# 3yp_project.net
KiCad netlist of a schematic drawn in EasyEDA
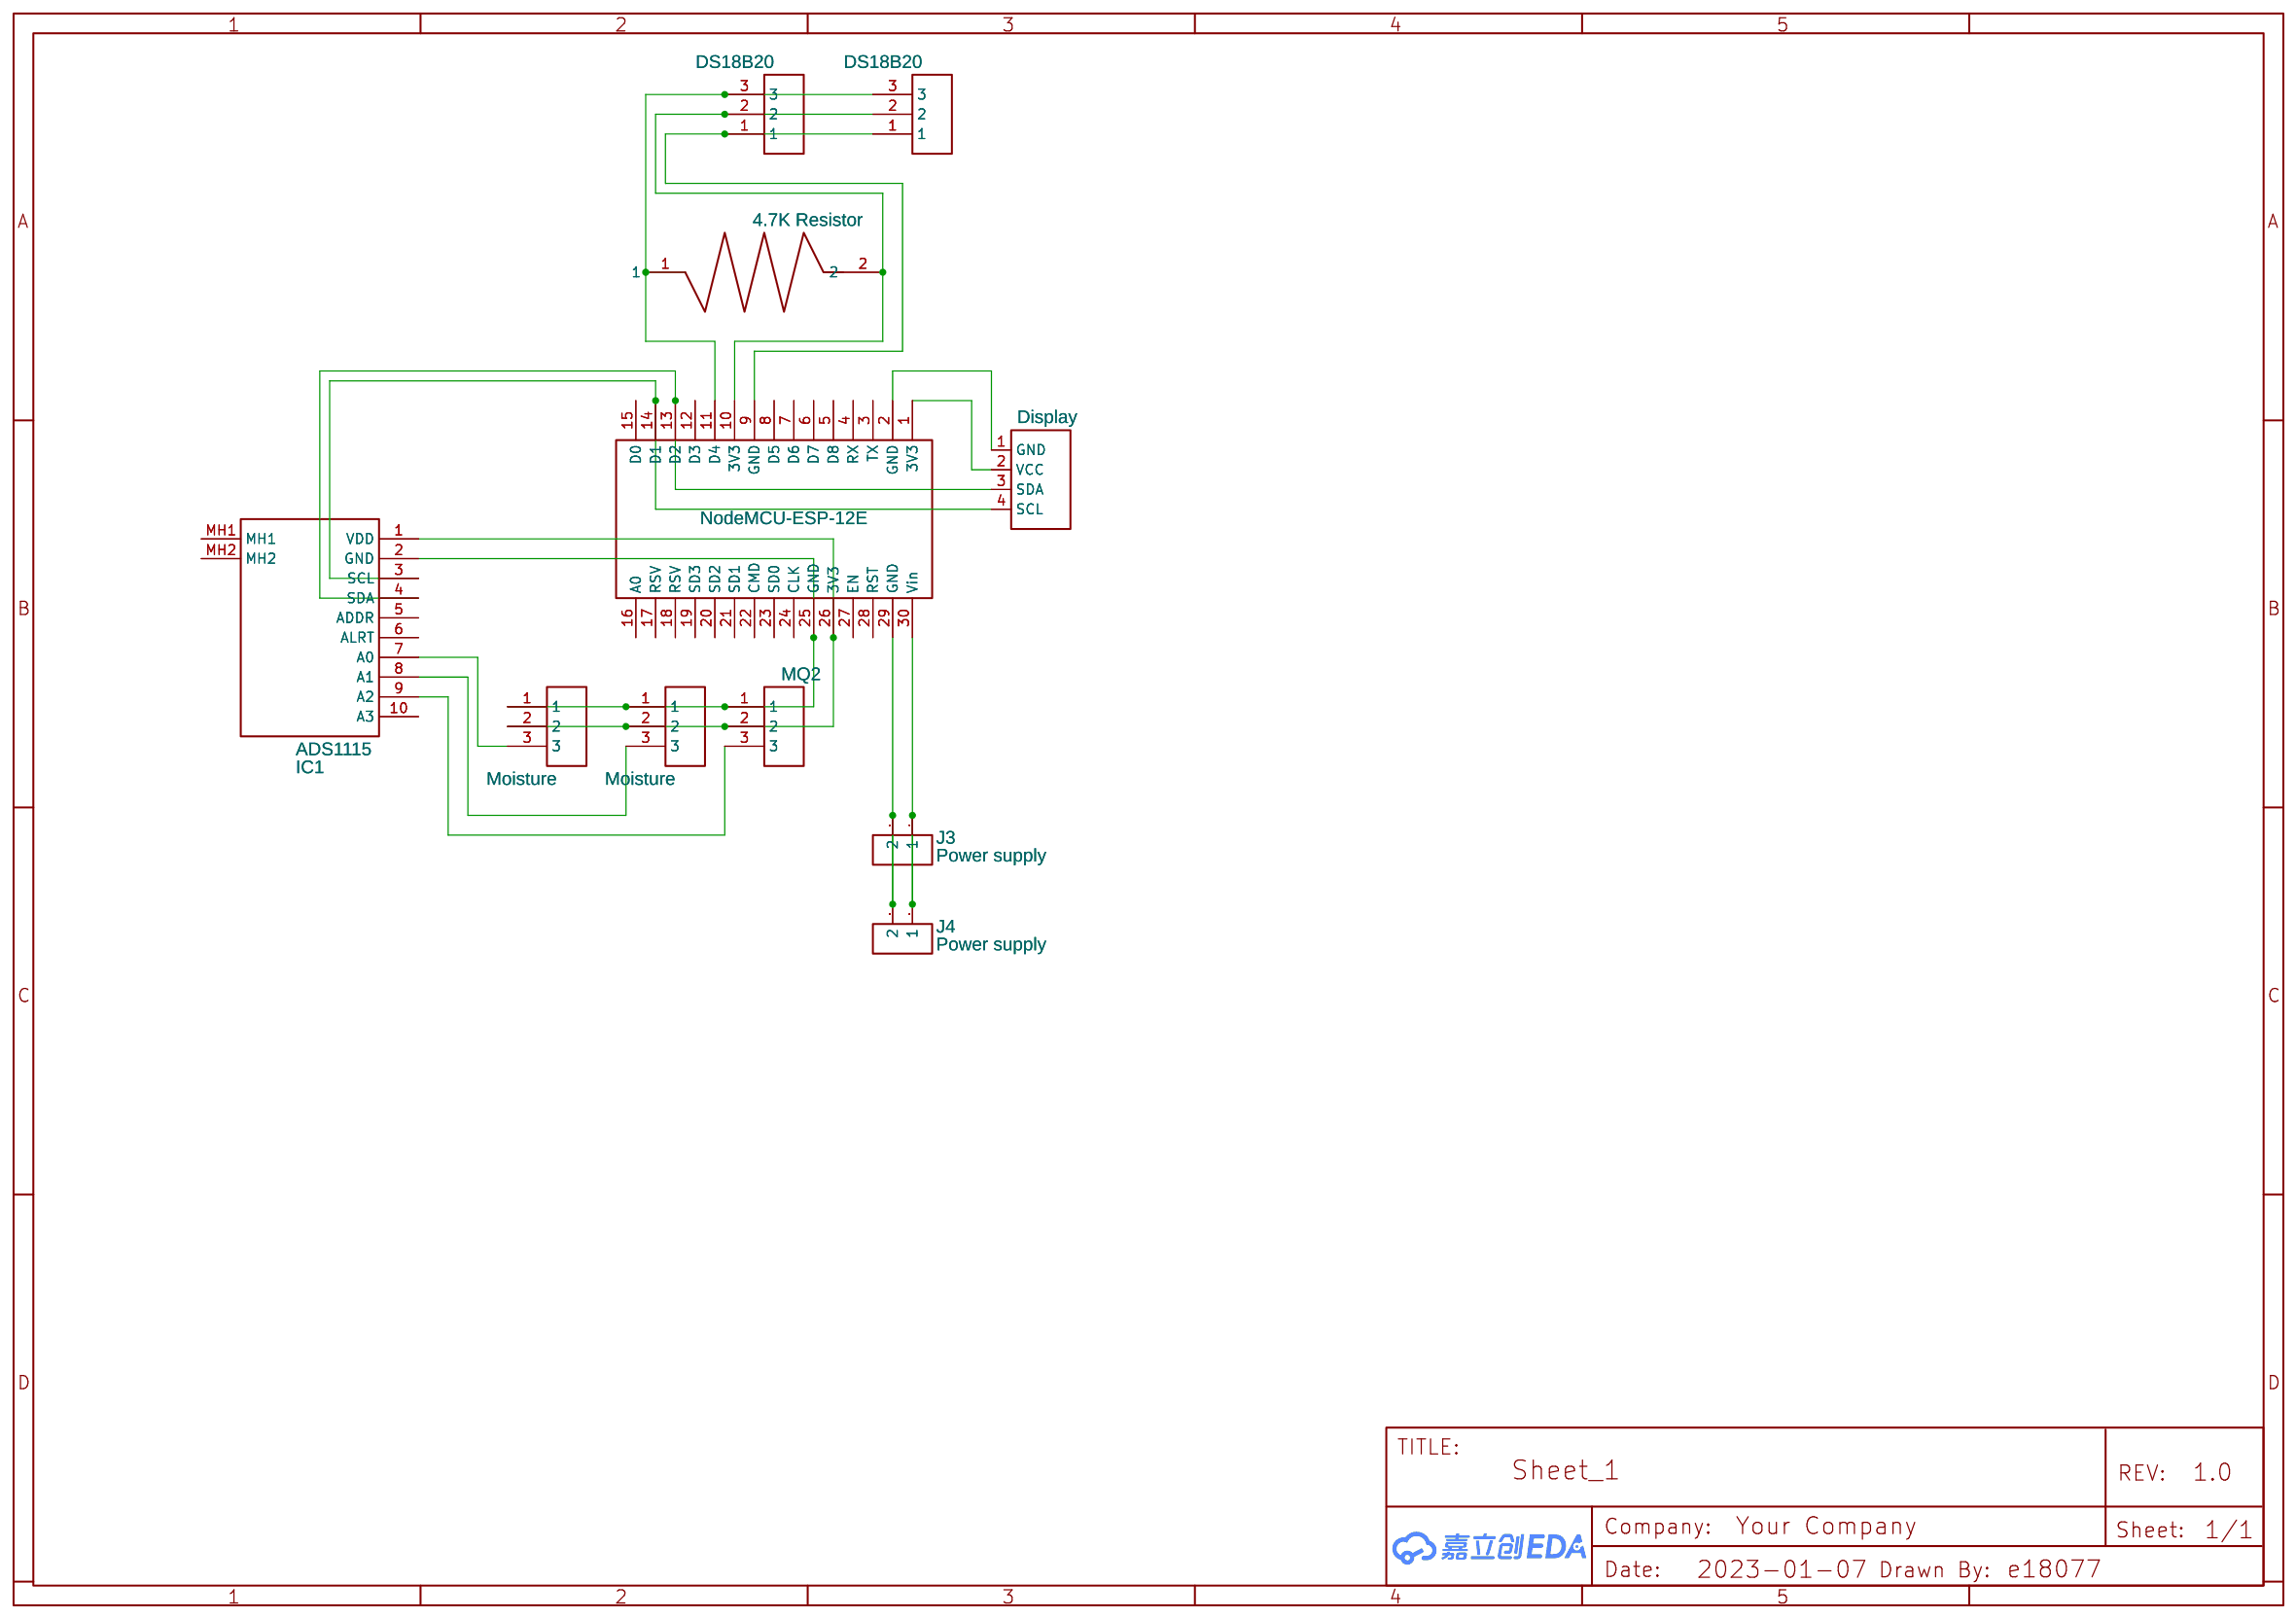
[diagram p0: Sheet_1]
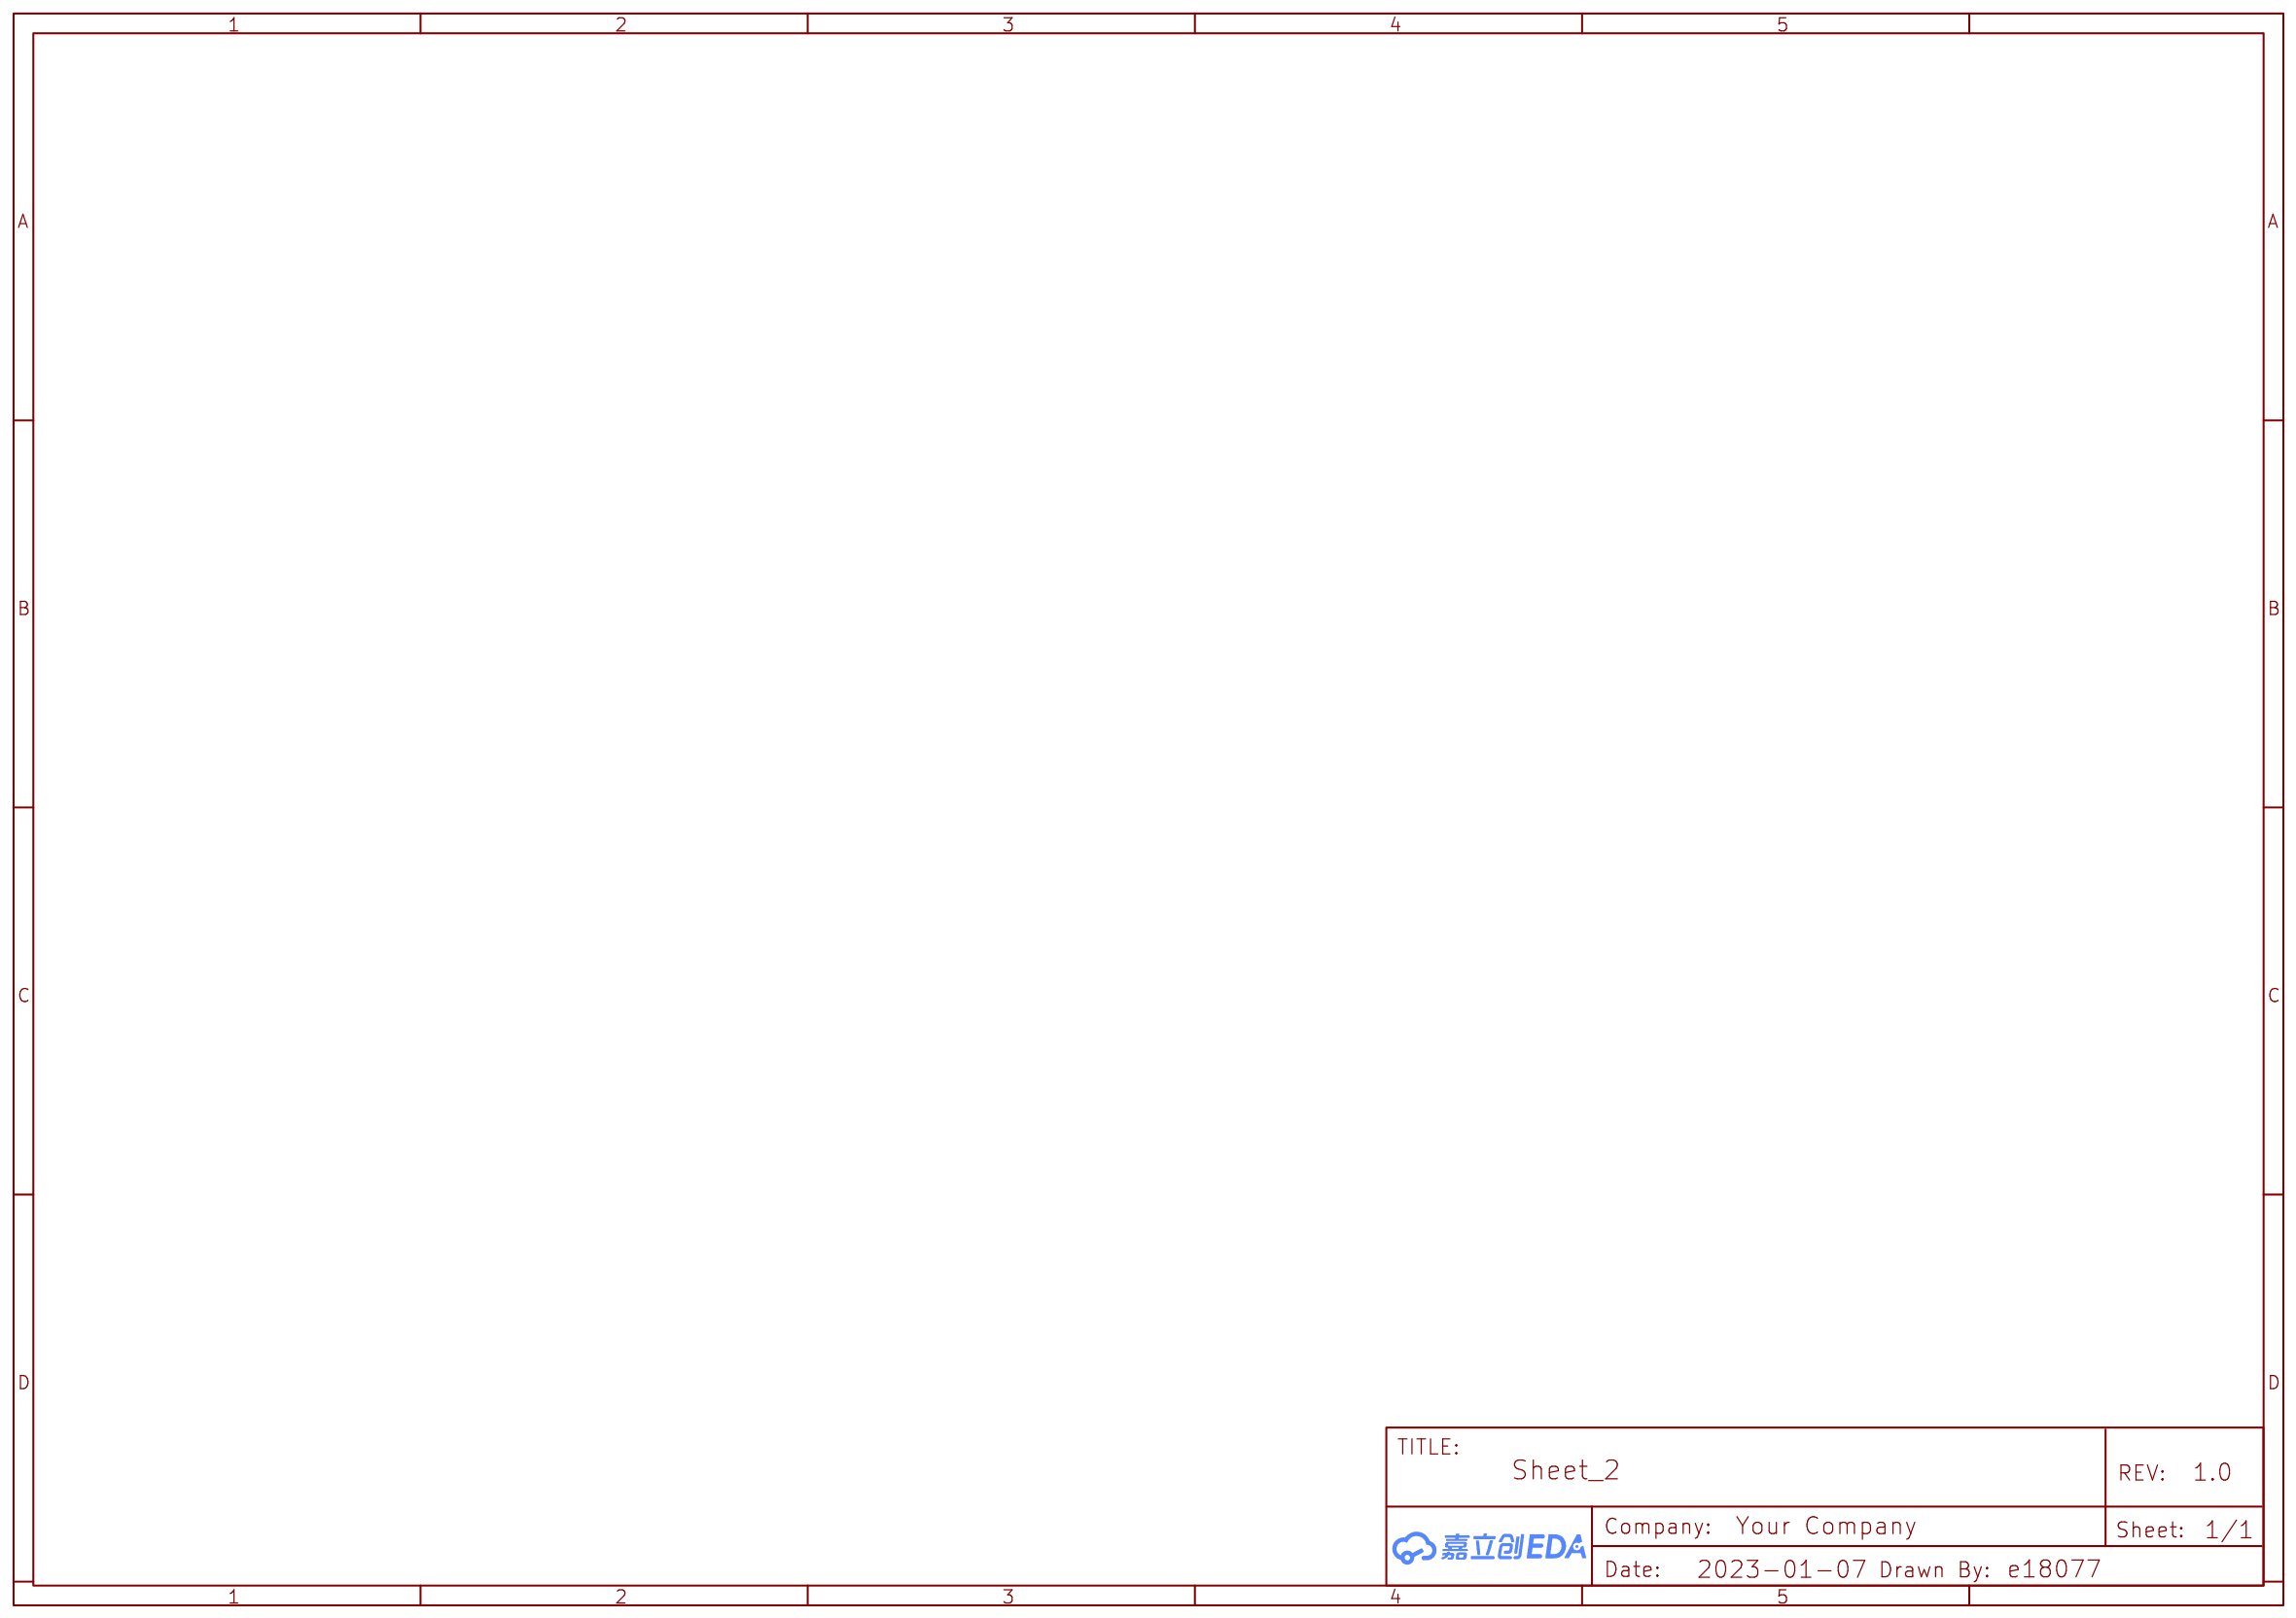
[diagram p1: Sheet_2]

(export (version "E")
  (design (tool "Eeschema 10.0.6"))
  (components
    (comp (ref "H1") (value "Display") (libsource (lib "") (part "I2C_HEADER LOWCOMOCO GND/VCC/SCL/SDA")))
    (comp (ref "H4") (value "DS18B20") (libsource (lib "") (part "HEADER-3PIN")))
    (comp (ref "H5") (value "DS18B20") (libsource (lib "") (part "HEADER-3PIN")))
    (comp (ref "H6") (value "MQ2") (libsource (lib "") (part "HEADER-3PIN_1")))
    (comp (ref "H7") (value "Moisture") (libsource (lib "") (part "HEADER-3PIN_1")))
    (comp (ref "H8") (value "Moisture") (libsource (lib "") (part "HEADER-3PIN_1")))
    (comp (ref "IC1") (value "ADS1115") (libsource (lib "") (part "ADS1115")))
    (comp (ref "J3")
      (value "Power supply")
      (fields
        (field (name "BOM_Manufacturer Part") "Female headerHDR1X8-2.54")
        (field (name "BOM_Supplier Part") "C27438")
      )
      (libsource (lib "") (part "HEADER PAD 2X"))
    )
    (comp (ref "J4")
      (value "Power supply")
      (fields
        (field (name "BOM_Manufacturer Part") "Female headerHDR1X8-2.54")
        (field (name "BOM_Supplier Part") "C27438")
      )
      (libsource (lib "") (part "HEADER PAD 2X"))
    )
    (comp (ref "U1") (value "NodeMCU-ESP-12E") (libsource (lib "") (part "NodeMCU-ESP-12E")))
    (comp (ref "U2") (value "4.7K Resistor") (libsource (lib "") (part "4.7K Resistor")))
  )
  (nets
    (net (code "1") (name "Net-(H1-GND)") (class "Default")
      (node (ref "H1") (pin "1") (pinfunction "GND_1") (pintype "input"))
      (node (ref "U1") (pin "2") (pinfunction "GND_2") (pintype "unspecified"))
    )
    (net (code "2") (name "Net-(H1-SCL)") (class "Default")
      (node (ref "H1") (pin "4") (pinfunction "SCL_4") (pintype "input"))
      (node (ref "IC1") (pin "3") (pinfunction "SCL_3") (pintype "unspecified"))
      (node (ref "U1") (pin "14") (pinfunction "D1_14") (pintype "unspecified"))
    )
    (net (code "3") (name "Net-(H1-SDA)") (class "Default")
      (node (ref "H1") (pin "3") (pinfunction "SDA_3") (pintype "input"))
      (node (ref "IC1") (pin "4") (pinfunction "SDA_4") (pintype "unspecified"))
      (node (ref "U1") (pin "13") (pinfunction "D2_13") (pintype "unspecified"))
    )
    (net (code "4") (name "Net-(H1-VCC)") (class "Default")
      (node (ref "H1") (pin "2") (pinfunction "VCC_2") (pintype "input"))
      (node (ref "U1") (pin "1") (pinfunction "3V3_1") (pintype "unspecified"))
    )
    (net (code "5") (name "Net-(H4-Pad1)") (class "Default")
      (node (ref "H4") (pin "1") (pinfunction "1_1") (pintype "unspecified"))
      (node (ref "H5") (pin "1") (pinfunction "1_1") (pintype "unspecified"))
      (node (ref "U1") (pin "9") (pinfunction "GND_9") (pintype "unspecified"))
    )
    (net (code "6") (name "Net-(H4-Pad2)") (class "Default")
      (node (ref "H4") (pin "2") (pinfunction "2_2") (pintype "unspecified"))
      (node (ref "H5") (pin "2") (pinfunction "2_2") (pintype "unspecified"))
      (node (ref "U1") (pin "10") (pinfunction "3V3_10") (pintype "unspecified"))
      (node (ref "U2") (pin "2") (pinfunction "2_2") (pintype "unspecified"))
    )
    (net (code "7") (name "Net-(IC1-A0)") (class "Default")
      (node (ref "H8") (pin "3") (pinfunction "3_3") (pintype "unspecified"))
      (node (ref "IC1") (pin "7") (pinfunction "A0_7") (pintype "unspecified"))
    )
    (net (code "8") (name "Net-(IC1-A1)") (class "Default")
      (node (ref "H7") (pin "3") (pinfunction "3_3") (pintype "unspecified"))
      (node (ref "IC1") (pin "8") (pinfunction "A1_8") (pintype "unspecified"))
    )
    (net (code "9") (name "Net-(IC1-A2)") (class "Default")
      (node (ref "H6") (pin "3") (pinfunction "3_3") (pintype "unspecified"))
      (node (ref "IC1") (pin "9") (pinfunction "A2_9") (pintype "unspecified"))
    )
    (net (code "10") (name "Net-(IC1-GND)") (class "Default")
      (node (ref "H6") (pin "1") (pinfunction "1_1") (pintype "unspecified"))
      (node (ref "H7") (pin "1") (pinfunction "1_1") (pintype "unspecified"))
      (node (ref "H8") (pin "1") (pinfunction "1_1") (pintype "unspecified"))
      (node (ref "IC1") (pin "2") (pinfunction "GND_2") (pintype "unspecified"))
      (node (ref "U1") (pin "25") (pinfunction "GND_25") (pintype "unspecified"))
    )
    (net (code "11") (name "Net-(IC1-VDD)") (class "Default")
      (node (ref "H6") (pin "2") (pinfunction "2_2") (pintype "unspecified"))
      (node (ref "H7") (pin "2") (pinfunction "2_2") (pintype "unspecified"))
      (node (ref "H8") (pin "2") (pinfunction "2_2") (pintype "unspecified"))
      (node (ref "IC1") (pin "1") (pinfunction "VDD_1") (pintype "unspecified"))
      (node (ref "U1") (pin "26") (pinfunction "3V3_26") (pintype "unspecified"))
    )
    (net (code "12") (name "Net-(J3-Pad2)") (class "Default")
      (node (ref "J3") (pin "2") (pinfunction "2_2") (pintype "unspecified"))
      (node (ref "J4") (pin "2") (pinfunction "2_2") (pintype "unspecified"))
      (node (ref "U1") (pin "29") (pinfunction "GND_29") (pintype "unspecified"))
    )
    (net (code "13") (name "Net-(U1-D4)") (class "Default")
      (node (ref "H4") (pin "3") (pinfunction "3_3") (pintype "unspecified"))
      (node (ref "H5") (pin "3") (pinfunction "3_3") (pintype "unspecified"))
      (node (ref "U1") (pin "11") (pinfunction "D4_11") (pintype "unspecified"))
      (node (ref "U2") (pin "1") (pinfunction "1_1") (pintype "unspecified"))
    )
    (net (code "14") (name "Net-(U1-Vin)") (class "Default")
      (node (ref "J3") (pin "1") (pinfunction "1_1") (pintype "unspecified"))
      (node (ref "J4") (pin "1") (pinfunction "1_1") (pintype "unspecified"))
      (node (ref "U1") (pin "30") (pinfunction "Vin_30") (pintype "unspecified"))
    )
    (net (code "15") (name "unconnected-(IC1-A3-Pad10)") (class "Default")
      (node (ref "IC1") (pin "10") (pinfunction "A3_10") (pintype "unspecified"))
    )
    (net (code "16") (name "unconnected-(IC1-ADDR-Pad5)") (class "Default")
      (node (ref "IC1") (pin "5") (pinfunction "ADDR_5") (pintype "unspecified"))
    )
    (net (code "17") (name "unconnected-(IC1-ALRT-Pad6)") (class "Default")
      (node (ref "IC1") (pin "6") (pinfunction "ALRT_6") (pintype "unspecified"))
    )
    (net (code "18") (name "unconnected-(IC1-PadMH1)") (class "Default")
      (node (ref "IC1") (pin "MH1") (pinfunction "MH1_MH1") (pintype "unspecified"))
    )
    (net (code "19") (name "unconnected-(IC1-PadMH2)") (class "Default")
      (node (ref "IC1") (pin "MH2") (pinfunction "MH2_MH2") (pintype "unspecified"))
    )
    (net (code "20") (name "unconnected-(U1-A0-Pad16)") (class "Default")
      (node (ref "U1") (pin "16") (pinfunction "A0_16") (pintype "unspecified"))
    )
    (net (code "21") (name "unconnected-(U1-CLK-Pad24)") (class "Default")
      (node (ref "U1") (pin "24") (pinfunction "CLK_24") (pintype "unspecified"))
    )
    (net (code "22") (name "unconnected-(U1-CMD-Pad22)") (class "Default")
      (node (ref "U1") (pin "22") (pinfunction "CMD_22") (pintype "unspecified"))
    )
    (net (code "23") (name "unconnected-(U1-D0-Pad15)") (class "Default")
      (node (ref "U1") (pin "15") (pinfunction "D0_15") (pintype "unspecified"))
    )
    (net (code "24") (name "unconnected-(U1-D3-Pad12)") (class "Default")
      (node (ref "U1") (pin "12") (pinfunction "D3_12") (pintype "unspecified"))
    )
    (net (code "25") (name "unconnected-(U1-D5-Pad8)") (class "Default")
      (node (ref "U1") (pin "8") (pinfunction "D5_8") (pintype "unspecified"))
    )
    (net (code "26") (name "unconnected-(U1-D6-Pad7)") (class "Default")
      (node (ref "U1") (pin "7") (pinfunction "D6_7") (pintype "unspecified"))
    )
    (net (code "27") (name "unconnected-(U1-D7-Pad6)") (class "Default")
      (node (ref "U1") (pin "6") (pinfunction "D7_6") (pintype "unspecified"))
    )
    (net (code "28") (name "unconnected-(U1-D8-Pad5)") (class "Default")
      (node (ref "U1") (pin "5") (pinfunction "D8_5") (pintype "unspecified"))
    )
    (net (code "29") (name "unconnected-(U1-EN-Pad27)") (class "Default")
      (node (ref "U1") (pin "27") (pinfunction "EN_27") (pintype "unspecified"))
    )
    (net (code "30") (name "unconnected-(U1-RST-Pad28)") (class "Default")
      (node (ref "U1") (pin "28") (pinfunction "RST_28") (pintype "unspecified"))
    )
    (net (code "31") (name "unconnected-(U1-RSV-Pad17)") (class "Default")
      (node (ref "U1") (pin "17") (pinfunction "RSV_17") (pintype "unspecified"))
    )
    (net (code "32") (name "unconnected-(U1-RSV-Pad18)") (class "Default")
      (node (ref "U1") (pin "18") (pinfunction "RSV_18") (pintype "unspecified"))
    )
    (net (code "33") (name "unconnected-(U1-RX-Pad4)") (class "Default")
      (node (ref "U1") (pin "4") (pinfunction "RX_4") (pintype "unspecified"))
    )
    (net (code "34") (name "unconnected-(U1-SD0-Pad23)") (class "Default")
      (node (ref "U1") (pin "23") (pinfunction "SD0_23") (pintype "unspecified"))
    )
    (net (code "35") (name "unconnected-(U1-SD1-Pad21)") (class "Default")
      (node (ref "U1") (pin "21") (pinfunction "SD1_21") (pintype "unspecified"))
    )
    (net (code "36") (name "unconnected-(U1-SD2-Pad20)") (class "Default")
      (node (ref "U1") (pin "20") (pinfunction "SD2_20") (pintype "unspecified"))
    )
    (net (code "37") (name "unconnected-(U1-SD3-Pad19)") (class "Default")
      (node (ref "U1") (pin "19") (pinfunction "SD3_19") (pintype "unspecified"))
    )
    (net (code "38") (name "unconnected-(U1-TX-Pad3)") (class "Default")
      (node (ref "U1") (pin "3") (pinfunction "TX_3") (pintype "unspecified"))
    )
  )
)
